# WiFi.net
KiCad netlist of a schematic drawn in Altium Designer
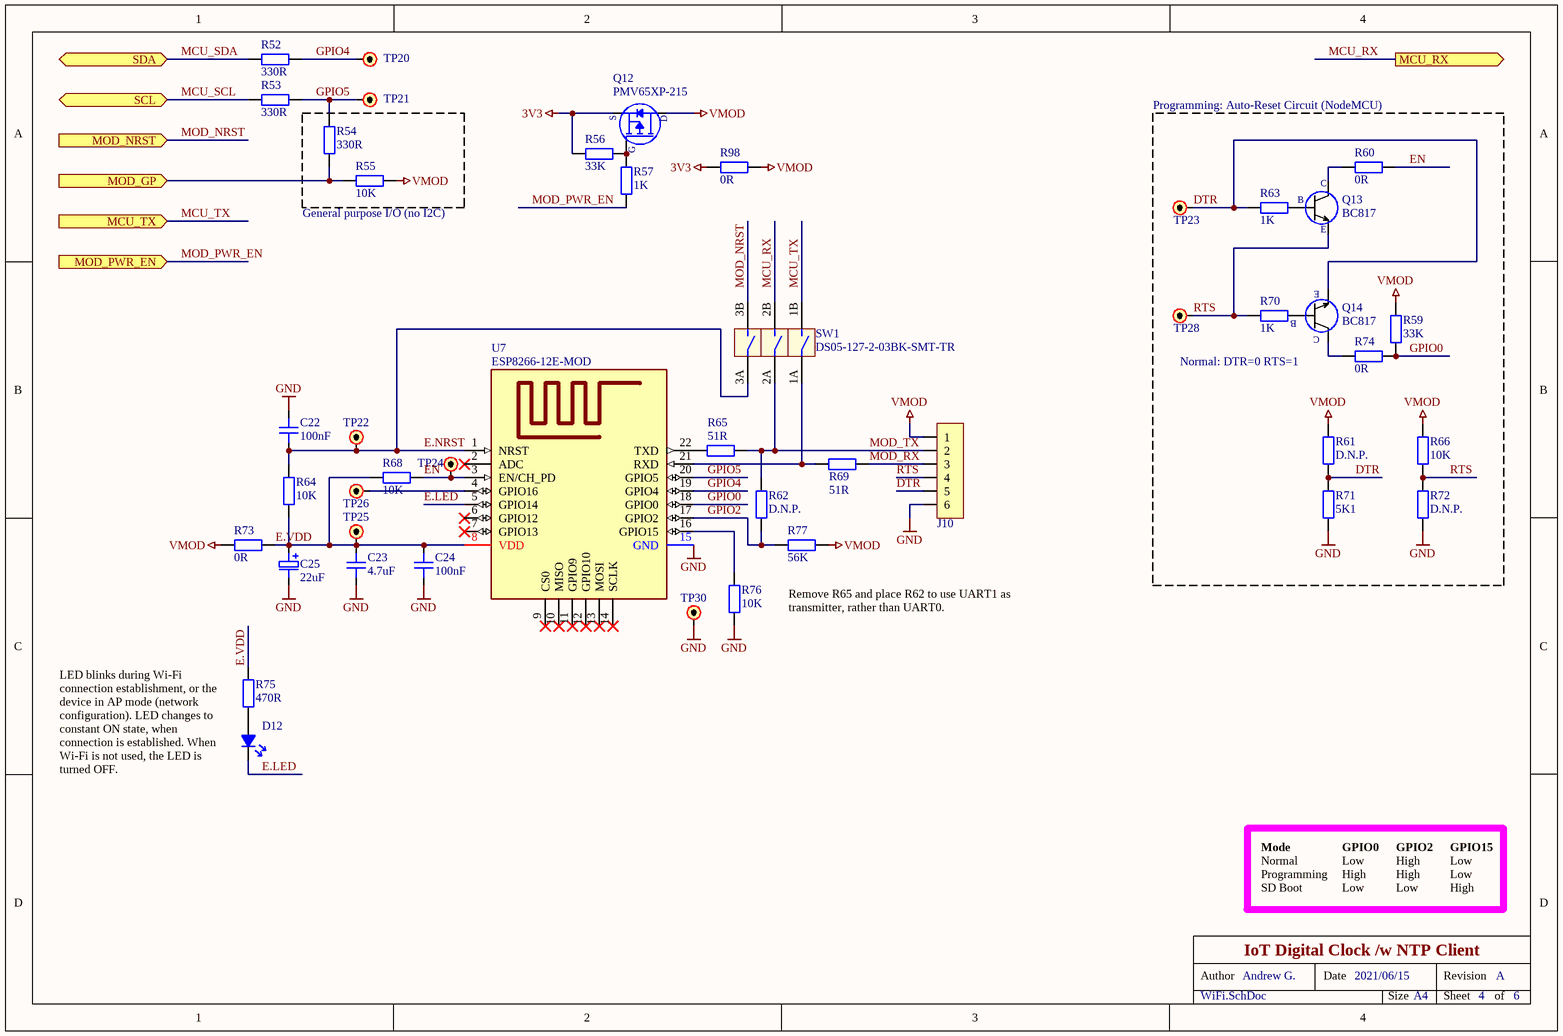
[diagram p0: WiFi.SchDoc]

(export (version "E")
  (design (tool "Eeschema 10.0.6"))
  (components
    (comp (ref "C22")
      (value "100nF")
      (footprint "0805C_RF_M")
      (description "Capacitor")
      (fields (field (name "TOLERANCE") "?") (field (name "MANUFACTURER") "Generic Brand"))
      (libsource (lib "AG.Generic") (part "C"))
    )
    (comp (ref "C23")
      (value "4.7uF")
      (footprint "0805C_RF_M")
      (description "Capacitor")
      (fields (field (name "TOLERANCE") "?") (field (name "MANUFACTURER") "Generic Brand"))
      (libsource (lib "AG.Generic") (part "C"))
    )
    (comp (ref "C24")
      (value "100nF")
      (footprint "0805C_RF_M")
      (description "Capacitor")
      (fields (field (name "TOLERANCE") "?") (field (name "MANUFACTURER") "Generic Brand"))
      (libsource (lib "AG.Generic") (part "C"))
    )
    (comp (ref "C25")
      (value "22uF")
      (footprint "C_EL_B_4MM_RF_M")
      (description "Polarized Capacitor")
      (fields (field (name "TOLERANCE") "?") (field (name "MANUFACTURER") "Generic Brand"))
      (libsource (lib "AG.Generic") (part "C-P"))
    )
    (comp (ref "D12")
      (value "Unspecified")
      (footprint "1206LED_RF_M")
      (description "LED")
      (fields (field (name "MANUFACTURER") "Generic Brand"))
      (libsource (lib "AG.Generic") (part "LED"))
    )
    (comp (ref "J10")
      (value "PINHDR-6P1")
      (footprint "HEADER-2.54-6P1")
      (description "Pin Header Single Row 6 Positions")
      (libsource (lib "AG.Connectors") (part "PINHDR-6P1"))
    )
    (comp (ref "Q12")
      (value "PMV65XP-215")
      (footprint "IRLML_SOT-23")
      (description "MOSFET P-CH 20V 2.8A 23SOT")
      (fields (field (name "ALTERNATIVE SUPPLIER PART NO") "9000037397"))
      (libsource (lib "AG.Discrete") (part "PMV65XP-215"))
    )
    (comp (ref "Q13")
      (value "BC817")
      (footprint "NXP_SOT-23_RF_M")
      (description "TRANS NPN 45V 0.5A SOT23")
      (fields
        (field (name "MANUFACTURER") "Nexperia USA Inc.")
        (field (name "MANUFACTURER PART NO") "BC817-40,215")
      )
      (libsource (lib "AG.Discrete") (part "BC817-40-215"))
    )
    (comp (ref "Q14")
      (value "BC817")
      (footprint "NXP_SOT-23_RF_M")
      (description "TRANS NPN 45V 0.5A SOT23")
      (fields
        (field (name "MANUFACTURER") "Nexperia USA Inc.")
        (field (name "MANUFACTURER PART NO") "BC817-40,215")
      )
      (libsource (lib "AG.Discrete") (part "BC817-40-215"))
    )
    (comp (ref "R52")
      (value "330R")
      (footprint "0805R_RF_M")
      (description "Resistor")
      (fields (field (name "TOLERANCE") "?") (field (name "MANUFACTURER") "Generic Brand"))
      (libsource (lib "AG.Generic") (part "R"))
    )
    (comp (ref "R53")
      (value "330R")
      (footprint "0805R_RF_M")
      (description "Resistor")
      (fields (field (name "TOLERANCE") "?") (field (name "MANUFACTURER") "Generic Brand"))
      (libsource (lib "AG.Generic") (part "R"))
    )
    (comp (ref "R54")
      (value "330R")
      (footprint "0805R_RF_M")
      (description "Resistor")
      (fields (field (name "TOLERANCE") "?") (field (name "MANUFACTURER") "Generic Brand"))
      (libsource (lib "AG.Generic") (part "R"))
    )
    (comp (ref "R55")
      (value "10K")
      (footprint "0805R_RF_M")
      (description "Resistor")
      (fields (field (name "TOLERANCE") "?") (field (name "MANUFACTURER") "Generic Brand"))
      (libsource (lib "AG.Generic") (part "R"))
    )
    (comp (ref "R56")
      (value "33K")
      (footprint "0805R_RF_M")
      (description "Resistor")
      (fields (field (name "TOLERANCE") "?") (field (name "MANUFACTURER") "Generic Brand"))
      (libsource (lib "AG.Generic") (part "R"))
    )
    (comp (ref "R57")
      (value "1K")
      (footprint "0805R_RF_M")
      (description "Resistor")
      (fields (field (name "TOLERANCE") "?") (field (name "MANUFACTURER") "Generic Brand"))
      (libsource (lib "AG.Generic") (part "R"))
    )
    (comp (ref "R59")
      (value "33K")
      (footprint "0805R_RF_M")
      (description "Resistor")
      (fields (field (name "TOLERANCE") "?") (field (name "MANUFACTURER") "Generic Brand"))
      (libsource (lib "AG.Generic") (part "R"))
    )
    (comp (ref "R60")
      (value "0R")
      (footprint "0805R_RF_M")
      (description "Resistor")
      (fields (field (name "TOLERANCE") "?") (field (name "MANUFACTURER") "Generic Brand"))
      (libsource (lib "AG.Generic") (part "R"))
    )
    (comp (ref "R61")
      (value "D.N.P.")
      (footprint "0805R_RF_M")
      (description "Resistor")
      (fields (field (name "TOLERANCE") "?") (field (name "MANUFACTURER") "Generic Brand"))
      (libsource (lib "AG.Generic") (part "R"))
    )
    (comp (ref "R62")
      (value "D.N.P.")
      (footprint "0805R_RF_M")
      (description "Resistor")
      (fields (field (name "TOLERANCE") "?") (field (name "MANUFACTURER") "Generic Brand"))
      (libsource (lib "AG.Generic") (part "R"))
    )
    (comp (ref "R63")
      (value "1K")
      (footprint "0805R_RF_M")
      (description "Resistor")
      (fields (field (name "TOLERANCE") "?") (field (name "MANUFACTURER") "Generic Brand"))
      (libsource (lib "AG.Generic") (part "R"))
    )
    (comp (ref "R64")
      (value "10K")
      (footprint "0805R_RF_M")
      (description "Resistor")
      (fields (field (name "TOLERANCE") "?") (field (name "MANUFACTURER") "Generic Brand"))
      (libsource (lib "AG.Generic") (part "R"))
    )
    (comp (ref "R65")
      (value "51R")
      (footprint "0805R_RF_M")
      (description "Resistor")
      (fields (field (name "TOLERANCE") "?") (field (name "MANUFACTURER") "Generic Brand"))
      (libsource (lib "AG.Generic") (part "R"))
    )
    (comp (ref "R66")
      (value "10K")
      (footprint "0805R_RF_M")
      (description "Resistor")
      (fields (field (name "TOLERANCE") "?") (field (name "MANUFACTURER") "Generic Brand"))
      (libsource (lib "AG.Generic") (part "R"))
    )
    (comp (ref "R68")
      (value "10K")
      (footprint "0805R_RF_M")
      (description "Resistor")
      (fields (field (name "TOLERANCE") "?") (field (name "MANUFACTURER") "Generic Brand"))
      (libsource (lib "AG.Generic") (part "R"))
    )
    (comp (ref "R69")
      (value "51R")
      (footprint "0805R_RF_M")
      (description "Resistor")
      (fields (field (name "TOLERANCE") "?") (field (name "MANUFACTURER") "Generic Brand"))
      (libsource (lib "AG.Generic") (part "R"))
    )
    (comp (ref "R70")
      (value "1K")
      (footprint "0805R_RF_M")
      (description "Resistor")
      (fields (field (name "TOLERANCE") "?") (field (name "MANUFACTURER") "Generic Brand"))
      (libsource (lib "AG.Generic") (part "R"))
    )
    (comp (ref "R71")
      (value "5K1")
      (footprint "0805R_RF_M")
      (description "Resistor")
      (fields (field (name "TOLERANCE") "?") (field (name "MANUFACTURER") "Generic Brand"))
      (libsource (lib "AG.Generic") (part "R"))
    )
    (comp (ref "R72")
      (value "D.N.P.")
      (footprint "0805R_RF_M")
      (description "Resistor")
      (fields (field (name "TOLERANCE") "?") (field (name "MANUFACTURER") "Generic Brand"))
      (libsource (lib "AG.Generic") (part "R"))
    )
    (comp (ref "R73")
      (value "0R")
      (footprint "0805R_RF_M")
      (description "Resistor")
      (fields (field (name "TOLERANCE") "?") (field (name "MANUFACTURER") "Generic Brand"))
      (libsource (lib "AG.Generic") (part "R"))
    )
    (comp (ref "R74")
      (value "0R")
      (footprint "0805R_RF_M")
      (description "Resistor")
      (fields (field (name "TOLERANCE") "?") (field (name "MANUFACTURER") "Generic Brand"))
      (libsource (lib "AG.Generic") (part "R"))
    )
    (comp (ref "R75")
      (value "470R")
      (footprint "0805R_RF_M")
      (description "Resistor")
      (fields (field (name "TOLERANCE") "?") (field (name "MANUFACTURER") "Generic Brand"))
      (libsource (lib "AG.Generic") (part "R"))
    )
    (comp (ref "R76")
      (value "10K")
      (footprint "0805R_RF_M")
      (description "Resistor")
      (fields (field (name "TOLERANCE") "?") (field (name "MANUFACTURER") "Generic Brand"))
      (libsource (lib "AG.Generic") (part "R"))
    )
    (comp (ref "R77")
      (value "56K")
      (footprint "0805R_RF_M")
      (description "Resistor")
      (fields (field (name "TOLERANCE") "?") (field (name "MANUFACTURER") "Generic Brand"))
      (libsource (lib "AG.Generic") (part "R"))
    )
    (comp (ref "R98")
      (value "0R")
      (footprint "0805R_RF_M")
      (description "Resistor")
      (fields (field (name "TOLERANCE") "?") (field (name "MANUFACTURER") "Generic Brand"))
      (libsource (lib "AG.Generic") (part "R"))
    )
    (comp (ref "SW1")
      (value "DS05-127-2-03BK-SMT-TR")
      (footprint "DIP_SWITCH_3POS_1.27mm")
      (description "DIP SWITCH SPST 1.27 PITCH FL 3POS")
      (libsource (lib "AG.Electromechanical") (part "DS05-127-2-03BK-SMT-TR"))
    )
    (comp (ref "TP20")
      (value "G.4")
      (footprint "PAD_R_1MM")
      (description "Test Point / Pad")
      (libsource (lib "AG.Misc") (part "Test Point"))
    )
    (comp (ref "TP21")
      (value "G.5")
      (footprint "PAD_R_1MM")
      (description "Test Point / Pad")
      (libsource (lib "AG.Misc") (part "Test Point"))
    )
    (comp (ref "TP22")
      (value "NRST")
      (footprint "PAD_R_1MM")
      (description "Test Point / Pad")
      (libsource (lib "AG.Misc") (part "Test Point"))
    )
    (comp (ref "TP23")
      (value "DTR")
      (footprint "PAD_R_1MM")
      (description "Test Point / Pad")
      (libsource (lib "AG.Misc") (part "Test Point"))
    )
    (comp (ref "TP24")
      (value "CH_PD")
      (footprint "PAD_R_1MM")
      (description "Test Point / Pad")
      (libsource (lib "AG.Misc") (part "Test Point"))
    )
    (comp (ref "TP25")
      (value "E.VDD")
      (footprint "PAD_R_1.5MM")
      (description "Test Point / Pad")
      (libsource (lib "AG.Misc") (part "Test Point"))
    )
    (comp (ref "TP26")
      (value "WAKE")
      (footprint "PAD_R_1MM")
      (description "Test Point / Pad")
      (libsource (lib "AG.Misc") (part "Test Point"))
    )
    (comp (ref "TP28")
      (value "RTS")
      (footprint "PAD_R_1MM")
      (description "Test Point / Pad")
      (libsource (lib "AG.Misc") (part "Test Point"))
    )
    (comp (ref "TP30")
      (value "GND")
      (footprint "PAD_R_1.5MM")
      (description "Test Point / Pad")
      (libsource (lib "AG.Misc") (part "Test Point"))
    )
    (comp (ref "U7")
      (value "ESP8266-12E-MOD")
      (footprint "ESP8266-12E-NBP-MOD")
      (description "RX TXRX MOD WIFI TRACE ANT SMD")
      (fields (field (name "MANUFACTURER") "Adafruit Industries LLC"))
      (libsource (lib "AG.Modules") (part "ESP8266-12E-MOD"))
    )
  )
  (nets
    (net (code "1") (name "/DTR") (class "Default")
      (node (ref "J10") (pin "5") (pinfunction "5_5") (pintype "passive"))
      (node (ref "Q14") (pin "2") (pinfunction "Emmiter_2") (pintype "passive"))
      (node (ref "R61") (pin "2") (pintype "passive"))
      (node (ref "R63") (pin "1") (pintype "passive"))
      (node (ref "R71") (pin "1") (pintype "passive"))
      (node (ref "TP23") (pin "1") (pinfunction "1_1") (pintype "passive"))
    )
    (net (code "2") (name "/E.LED") (class "Default")
      (node (ref "D12") (pin "C") (pinfunction "C_C") (pintype "passive"))
      (node (ref "U7") (pin "5") (pinfunction "GPIO14_5") (pintype "bidirectional"))
    )
    (net (code "3") (name "/E.NRST") (class "Default")
      (node (ref "C22") (pin "2") (pinfunction "2_2") (pintype "passive"))
      (node (ref "R64") (pin "1") (pintype "passive"))
      (node (ref "SW1") (pin "3A") (pinfunction "3A_3A") (pintype "passive"))
      (node (ref "TP22") (pin "1") (pinfunction "1_1") (pintype "passive"))
      (node (ref "U7") (pin "1") (pinfunction "NRST_1") (pintype "input"))
    )
    (net (code "4") (name "/E.VDD") (class "Default")
      (node (ref "C23") (pin "2") (pinfunction "2_2") (pintype "passive"))
      (node (ref "C24") (pin "2") (pinfunction "2_2") (pintype "passive"))
      (node (ref "C25") (pin "P") (pinfunction "P_P") (pintype "power_in"))
      (node (ref "R64") (pin "2") (pintype "passive"))
      (node (ref "R68") (pin "1") (pintype "passive"))
      (node (ref "R73") (pin "1") (pintype "passive"))
      (node (ref "R75") (pin "1") (pintype "passive"))
      (node (ref "TP25") (pin "1") (pinfunction "1_1") (pintype "passive"))
      (node (ref "U7") (pin "8") (pinfunction "VDD_8") (pintype "passive"))
    )
    (net (code "5") (name "/EN") (class "Default")
      (node (ref "R60") (pin "2") (pintype "passive"))
      (node (ref "R68") (pin "2") (pintype "passive"))
      (node (ref "TP24") (pin "1") (pinfunction "1_1") (pintype "passive"))
      (node (ref "U7") (pin "3") (pinfunction "EN/CH_PD_3") (pintype "input"))
    )
    (net (code "6") (name "/GPIO0") (class "Default")
      (node (ref "R59") (pin "1") (pintype "passive"))
      (node (ref "R74") (pin "2") (pintype "passive"))
      (node (ref "U7") (pin "18") (pinfunction "GPIO0_18") (pintype "bidirectional"))
    )
    (net (code "7") (name "/GPIO2") (class "Default")
      (node (ref "R62") (pin "1") (pintype "passive"))
      (node (ref "R77") (pin "2") (pintype "passive"))
      (node (ref "U7") (pin "17") (pinfunction "GPIO2_17") (pintype "bidirectional"))
    )
    (net (code "8") (name "/GPIO4") (class "Default")
      (node (ref "R52") (pin "2") (pintype "passive"))
      (node (ref "TP20") (pin "1") (pinfunction "1_1") (pintype "passive"))
      (node (ref "U7") (pin "19") (pinfunction "GPIO4_19") (pintype "bidirectional"))
    )
    (net (code "9") (name "/GPIO5") (class "Default")
      (node (ref "R53") (pin "2") (pintype "passive"))
      (node (ref "R54") (pin "2") (pintype "passive"))
      (node (ref "TP21") (pin "1") (pinfunction "1_1") (pintype "passive"))
      (node (ref "U7") (pin "20") (pinfunction "GPIO5_20") (pintype "bidirectional"))
    )
    (net (code "10") (name "/MCU_RX") (class "Default")
      (node (ref "SW1") (pin "2B") (pinfunction "2B_2B") (pintype "passive"))
    )
    (net (code "11") (name "/MCU_SCL") (class "Default") (node (ref "R53") (pin "1") (pintype "passive")))
    (net (code "12") (name "/MCU_SDA") (class "Default") (node (ref "R52") (pin "1") (pintype "passive")))
    (net (code "13") (name "/MCU_TX") (class "Default")
      (node (ref "SW1") (pin "1B") (pinfunction "1B_1B") (pintype "passive"))
    )
    (net (code "14") (name "/MOD_GP") (class "Default")
      (node (ref "R54") (pin "1") (pintype "passive"))
      (node (ref "R55") (pin "1") (pintype "passive"))
    )
    (net (code "15") (name "/MOD_NRST") (class "Default")
      (node (ref "SW1") (pin "3B") (pinfunction "3B_3B") (pintype "passive"))
    )
    (net (code "16") (name "/MOD_PWR_EN") (class "Default") (node (ref "R57") (pin "1") (pintype "passive")))
    (net (code "17") (name "/MOD_RX") (class "Default")
      (node (ref "J10") (pin "3") (pinfunction "3_3") (pintype "passive"))
      (node (ref "R69") (pin "2") (pintype "passive"))
    )
    (net (code "18") (name "/MOD_TX") (class "Default")
      (node (ref "J10") (pin "2") (pinfunction "2_2") (pintype "passive"))
      (node (ref "R62") (pin "2") (pintype "passive"))
      (node (ref "R65") (pin "2") (pintype "passive"))
      (node (ref "SW1") (pin "2A") (pinfunction "2A_2A") (pintype "passive"))
    )
    (net (code "19") (name "/RTS") (class "Default")
      (node (ref "J10") (pin "4") (pinfunction "4_4") (pintype "passive"))
      (node (ref "Q13") (pin "2") (pinfunction "Emmiter_2") (pintype "passive"))
      (node (ref "R66") (pin "2") (pintype "passive"))
      (node (ref "R70") (pin "1") (pintype "passive"))
      (node (ref "R72") (pin "1") (pintype "passive"))
      (node (ref "TP28") (pin "1") (pinfunction "1_1") (pintype "passive"))
    )
    (net (code "20") (name "3V3") (class "Default")
      (node (ref "Q12") (pin "2") (pinfunction "Source_2") (pintype "passive"))
      (node (ref "R56") (pin "1") (pintype "passive"))
      (node (ref "R98") (pin "2") (pintype "passive"))
    )
    (net (code "21") (name "GND") (class "Default")
      (node (ref "C22") (pin "1") (pinfunction "1_1") (pintype "passive"))
      (node (ref "C23") (pin "1") (pinfunction "1_1") (pintype "passive"))
      (node (ref "C24") (pin "1") (pinfunction "1_1") (pintype "passive"))
      (node (ref "C25") (pin "N") (pinfunction "N_N") (pintype "power_in"))
      (node (ref "J10") (pin "6") (pinfunction "6_6") (pintype "passive"))
      (node (ref "R71") (pin "2") (pintype "passive"))
      (node (ref "R72") (pin "2") (pintype "passive"))
      (node (ref "R76") (pin "1") (pintype "passive"))
      (node (ref "TP30") (pin "1") (pinfunction "1_1") (pintype "passive"))
      (node (ref "U7") (pin "15") (pinfunction "GND_15") (pintype "passive"))
    )
    (net (code "22") (name "Net-(D12-PadA)") (class "Default")
      (node (ref "D12") (pin "A") (pinfunction "A_A") (pintype "passive"))
      (node (ref "R75") (pin "2") (pintype "passive"))
    )
    (net (code "23") (name "Net-(Q12-Gate)") (class "Default")
      (node (ref "Q12") (pin "1") (pinfunction "Gate_1") (pintype "passive"))
      (node (ref "R56") (pin "2") (pintype "passive"))
      (node (ref "R57") (pin "2") (pintype "passive"))
    )
    (net (code "24") (name "Net-(Q13-Base)") (class "Default")
      (node (ref "Q13") (pin "1") (pinfunction "Base_1") (pintype "passive"))
      (node (ref "R63") (pin "2") (pintype "passive"))
    )
    (net (code "25") (name "Net-(Q13-Collector)") (class "Default")
      (node (ref "Q13") (pin "3") (pinfunction "Collector_3") (pintype "passive"))
      (node (ref "R60") (pin "1") (pintype "passive"))
    )
    (net (code "26") (name "Net-(Q14-Base)") (class "Default")
      (node (ref "Q14") (pin "1") (pinfunction "Base_1") (pintype "passive"))
      (node (ref "R70") (pin "2") (pintype "passive"))
    )
    (net (code "27") (name "Net-(Q14-Collector)") (class "Default")
      (node (ref "Q14") (pin "3") (pinfunction "Collector_3") (pintype "passive"))
      (node (ref "R74") (pin "1") (pintype "passive"))
    )
    (net (code "28") (name "Net-(U7-GPIO15)") (class "Default")
      (node (ref "R76") (pin "2") (pintype "passive"))
      (node (ref "U7") (pin "16") (pinfunction "GPIO15_16") (pintype "bidirectional"))
    )
    (net (code "29") (name "Net-(U7-GPIO16)") (class "Default")
      (node (ref "TP26") (pin "1") (pinfunction "1_1") (pintype "passive"))
      (node (ref "U7") (pin "4") (pinfunction "GPIO16_4") (pintype "bidirectional"))
    )
    (net (code "30") (name "Net-(U7-RXD)") (class "Default")
      (node (ref "R69") (pin "1") (pintype "passive"))
      (node (ref "SW1") (pin "1A") (pinfunction "1A_1A") (pintype "passive"))
      (node (ref "U7") (pin "21") (pinfunction "RXD_21") (pintype "input"))
    )
    (net (code "31") (name "Net-(U7-TXD)") (class "Default")
      (node (ref "R65") (pin "1") (pintype "passive"))
      (node (ref "U7") (pin "22") (pinfunction "TXD_22") (pintype "output"))
    )
    (net (code "32") (name "VMOD") (class "Default")
      (node (ref "J10") (pin "1") (pinfunction "1_1") (pintype "passive"))
      (node (ref "Q12") (pin "3") (pinfunction "Drain_3") (pintype "passive"))
      (node (ref "R55") (pin "2") (pintype "passive"))
      (node (ref "R59") (pin "2") (pintype "passive"))
      (node (ref "R61") (pin "1") (pintype "passive"))
      (node (ref "R66") (pin "1") (pintype "passive"))
      (node (ref "R73") (pin "2") (pintype "passive"))
      (node (ref "R77") (pin "1") (pintype "passive"))
      (node (ref "R98") (pin "1") (pintype "passive"))
    )
    (net (code "33") (name "unconnected-(U7-ADC-Pad2)") (class "Default")
      (node (ref "U7") (pin "2") (pinfunction "ADC_2") (pintype "tri_state+no_connect"))
    )
    (net (code "34") (name "unconnected-(U7-CS0-Pad9)") (class "Default")
      (node (ref "U7") (pin "9") (pinfunction "CS0_9") (pintype "passive+no_connect"))
    )
    (net (code "35") (name "unconnected-(U7-GPIO9-Pad11)") (class "Default")
      (node (ref "U7") (pin "11") (pinfunction "GPIO9_11") (pintype "passive+no_connect"))
    )
    (net (code "36") (name "unconnected-(U7-GPIO10-Pad12)") (class "Default")
      (node (ref "U7") (pin "12") (pinfunction "GPIO10_12") (pintype "passive+no_connect"))
    )
    (net (code "37") (name "unconnected-(U7-GPIO12-Pad6)") (class "Default")
      (node (ref "U7") (pin "6") (pinfunction "GPIO12_6") (pintype "bidirectional+no_connect"))
    )
    (net (code "38") (name "unconnected-(U7-GPIO13-Pad7)") (class "Default")
      (node (ref "U7") (pin "7") (pinfunction "GPIO13_7") (pintype "bidirectional+no_connect"))
    )
    (net (code "39") (name "unconnected-(U7-MISO-Pad10)") (class "Default")
      (node (ref "U7") (pin "10") (pinfunction "MISO_10") (pintype "passive+no_connect"))
    )
    (net (code "40") (name "unconnected-(U7-MOSI-Pad13)") (class "Default")
      (node (ref "U7") (pin "13") (pinfunction "MOSI_13") (pintype "passive+no_connect"))
    )
    (net (code "41") (name "unconnected-(U7-SCLK-Pad14)") (class "Default")
      (node (ref "U7") (pin "14") (pinfunction "SCLK_14") (pintype "passive+no_connect"))
    )
  )
)
